# LIC_rack_BB-01.net
KiCad netlist of a schematic drawn in EAGLE
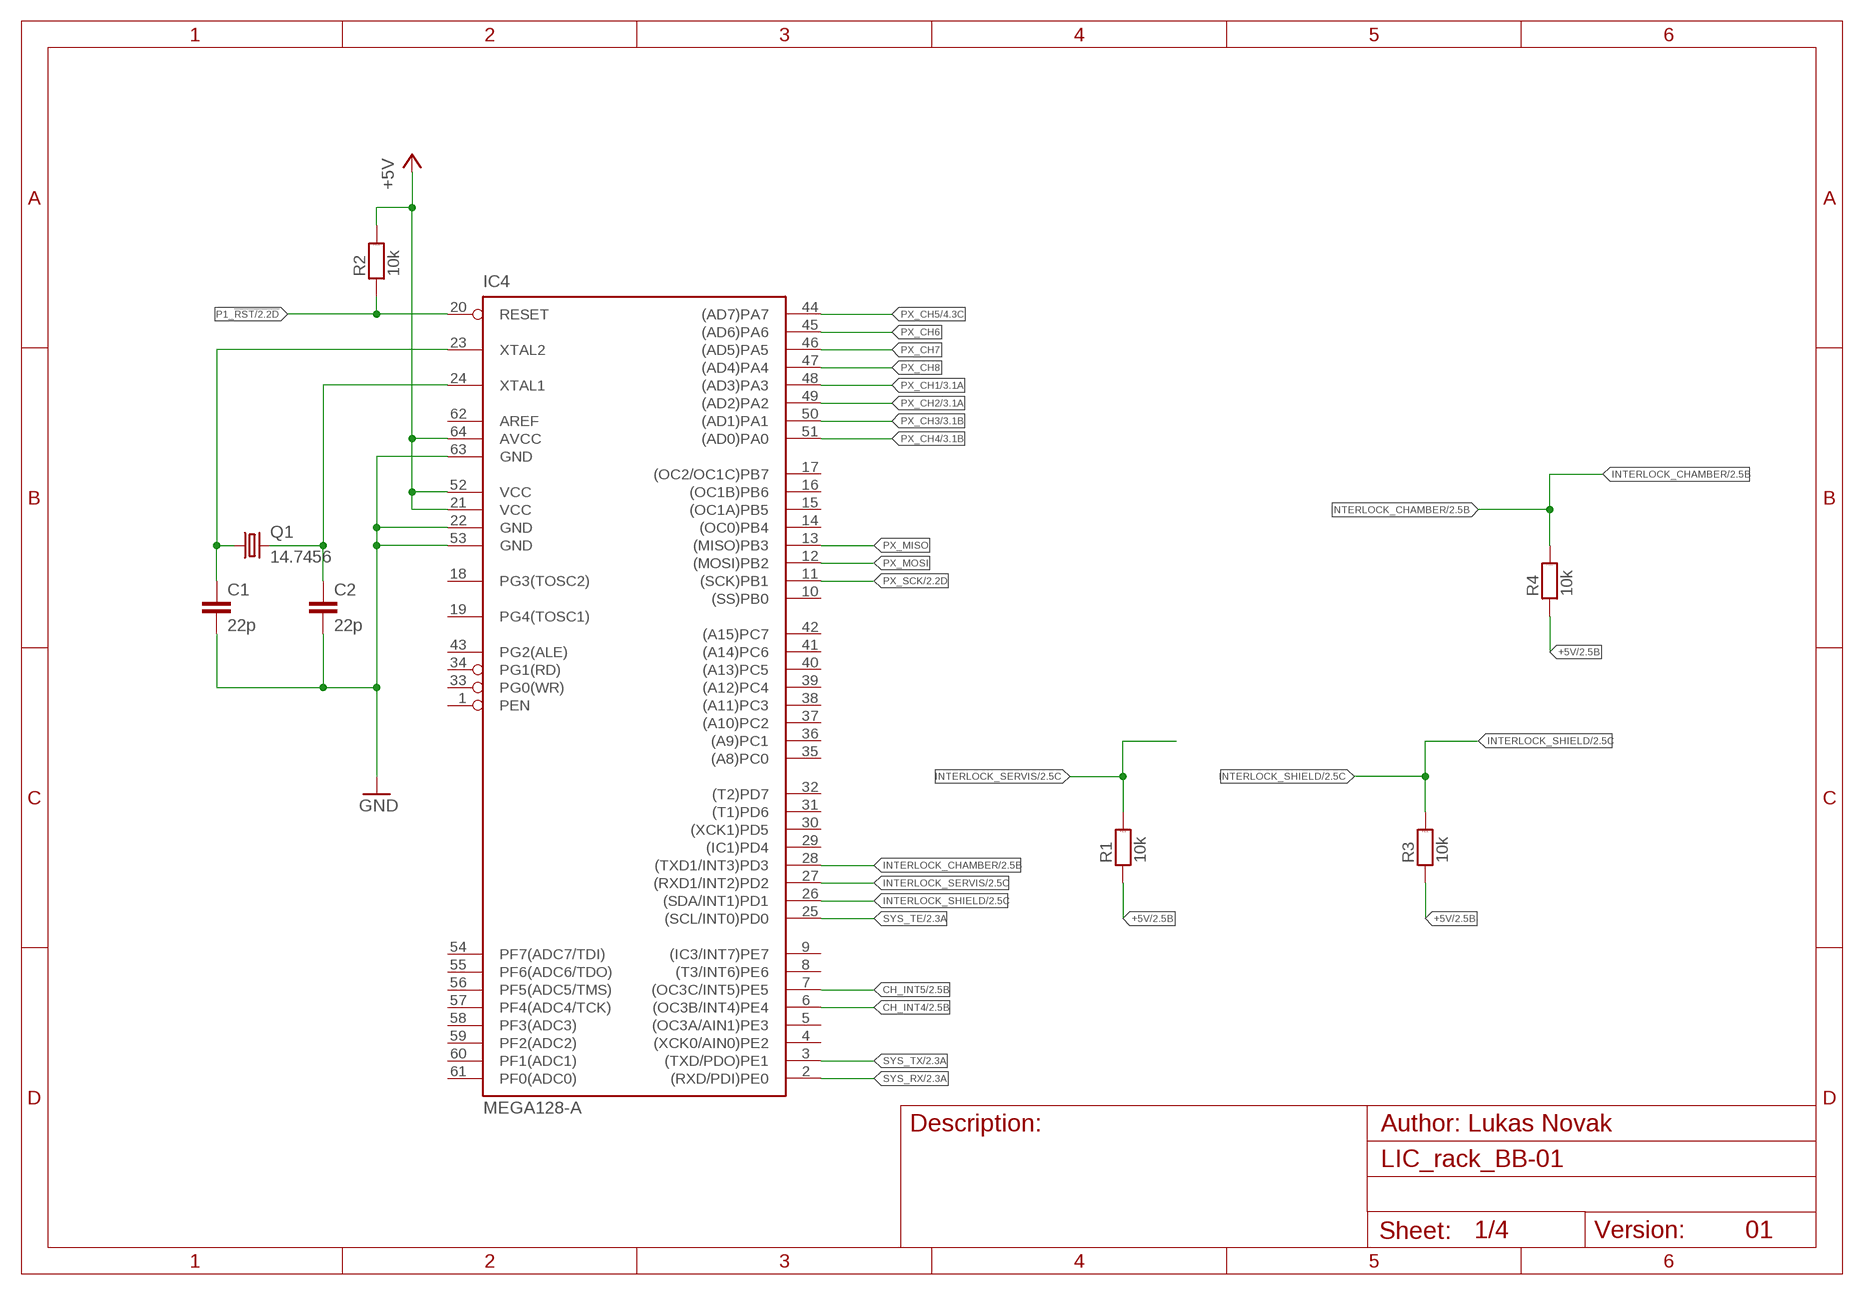
[diagram p0: schematic, sheet 1]
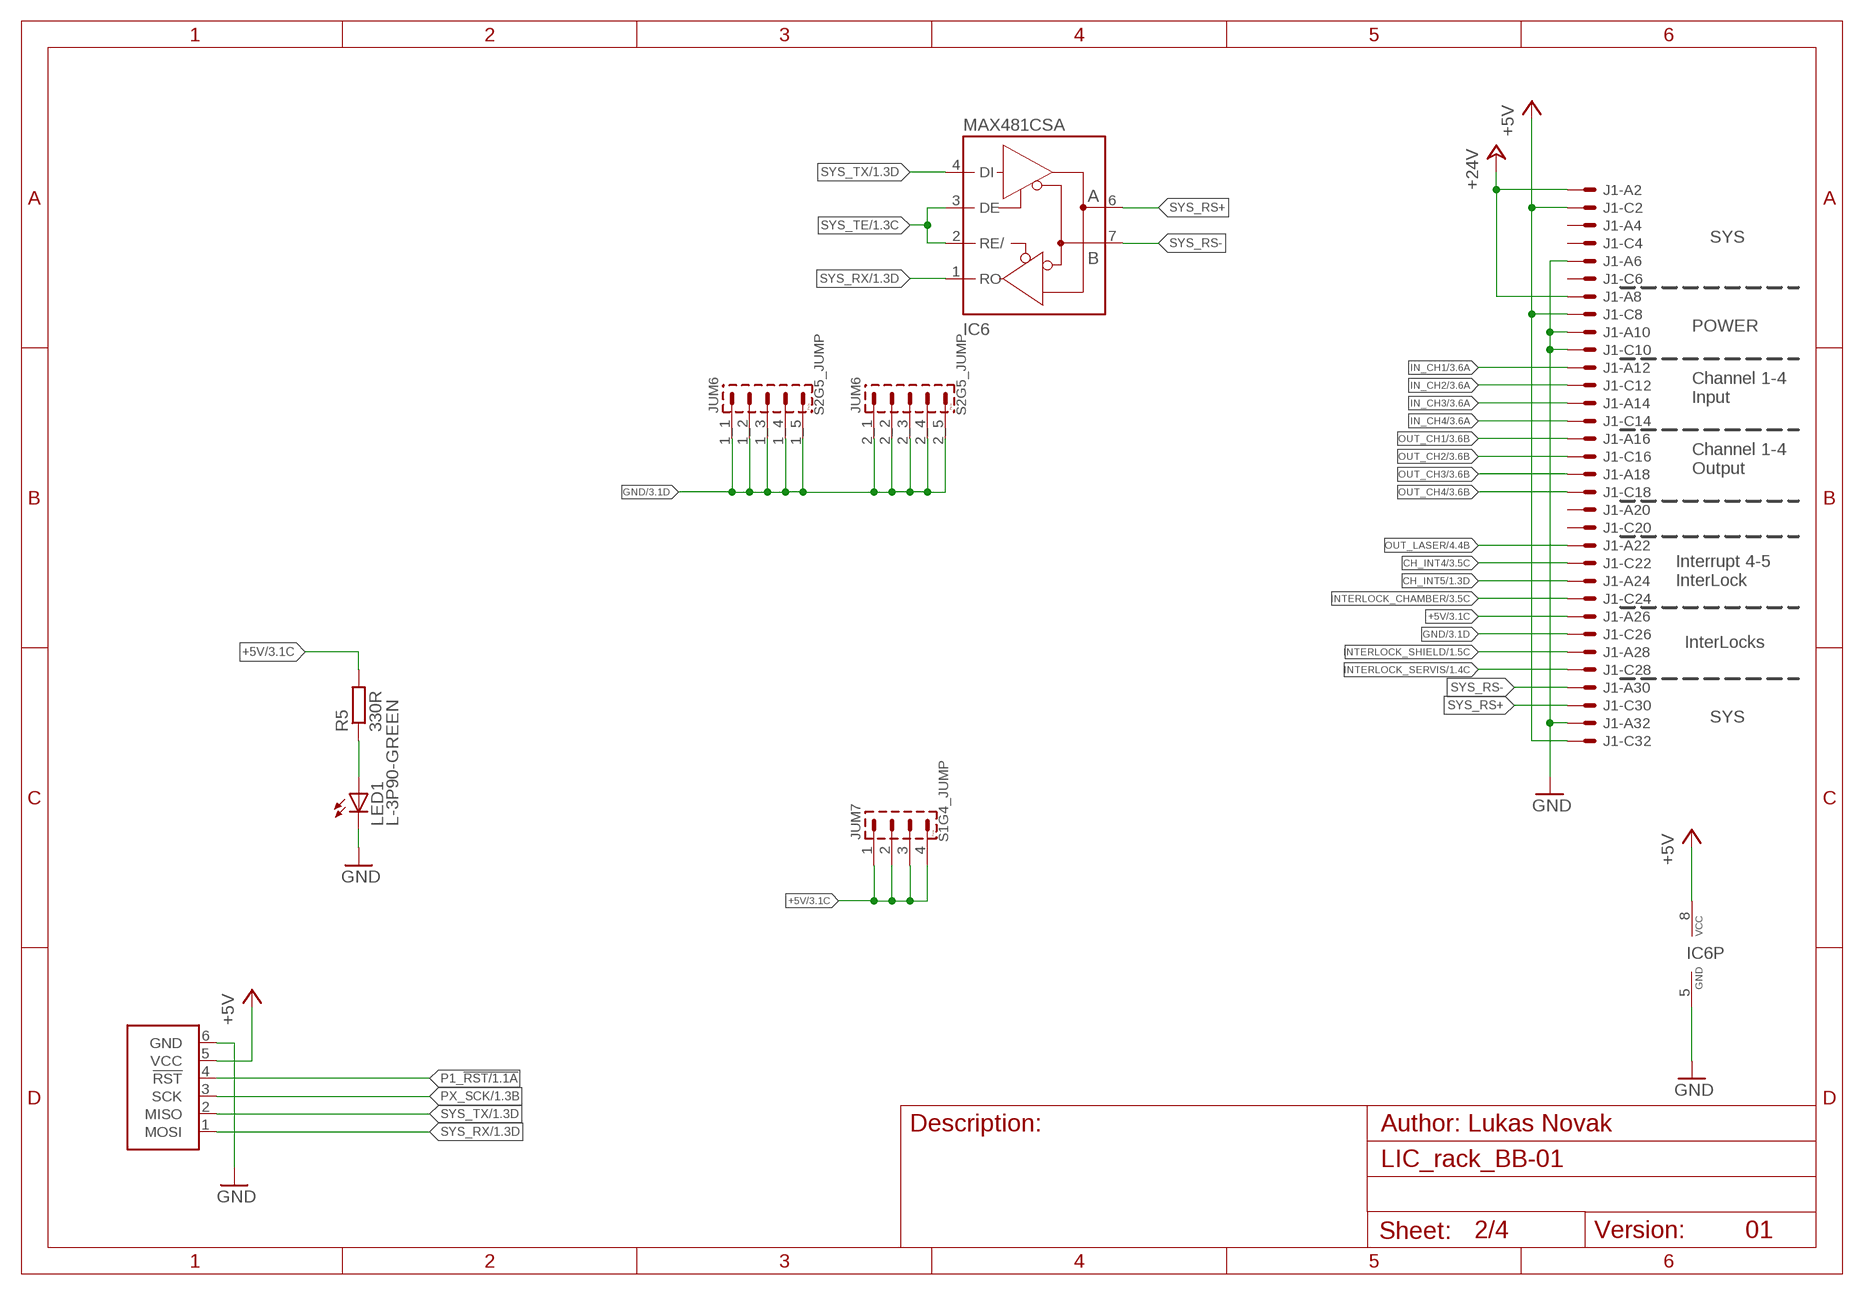
[diagram p1: schematic, sheet 2]
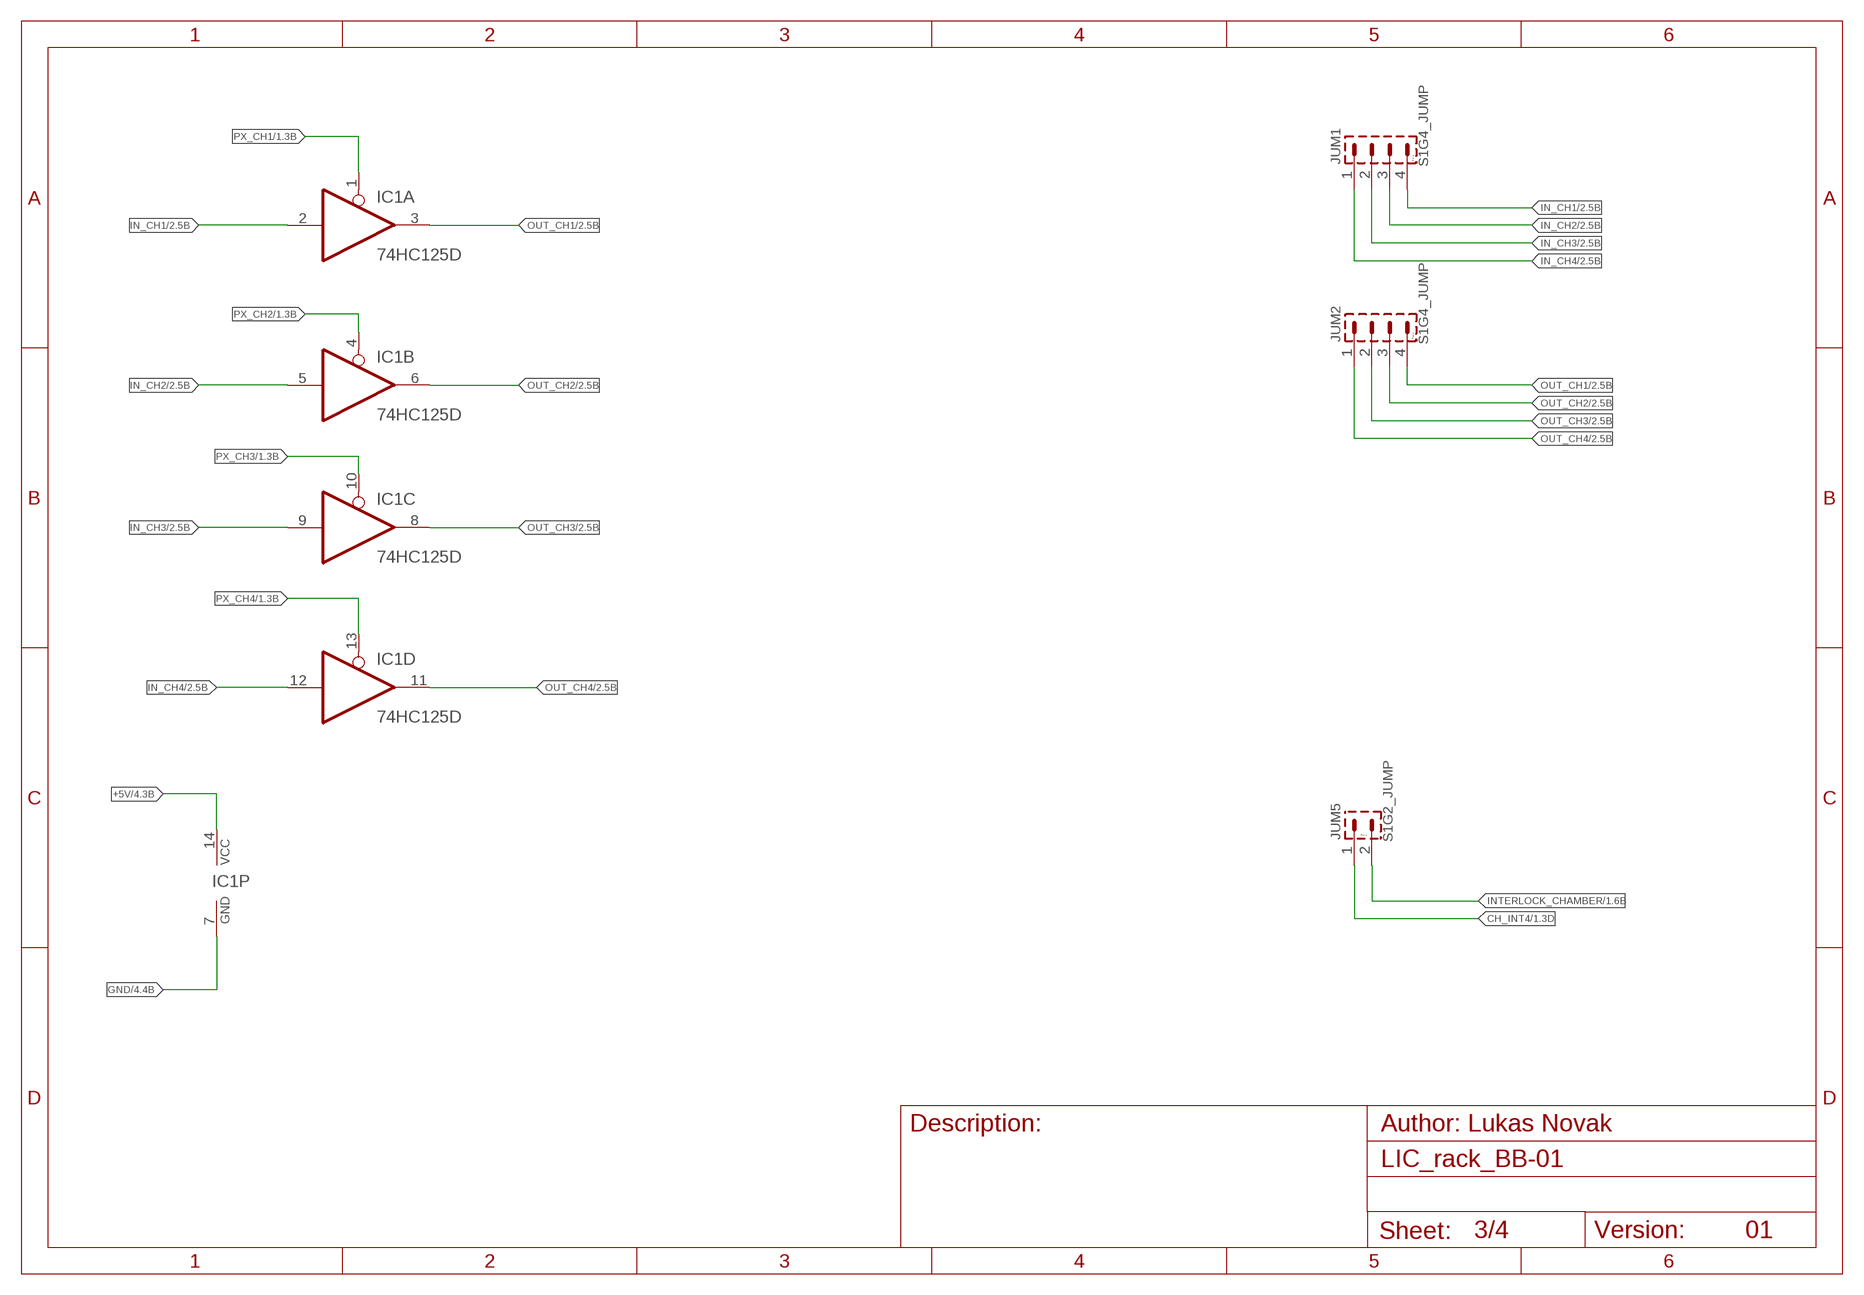
[diagram p2: schematic, sheet 3]
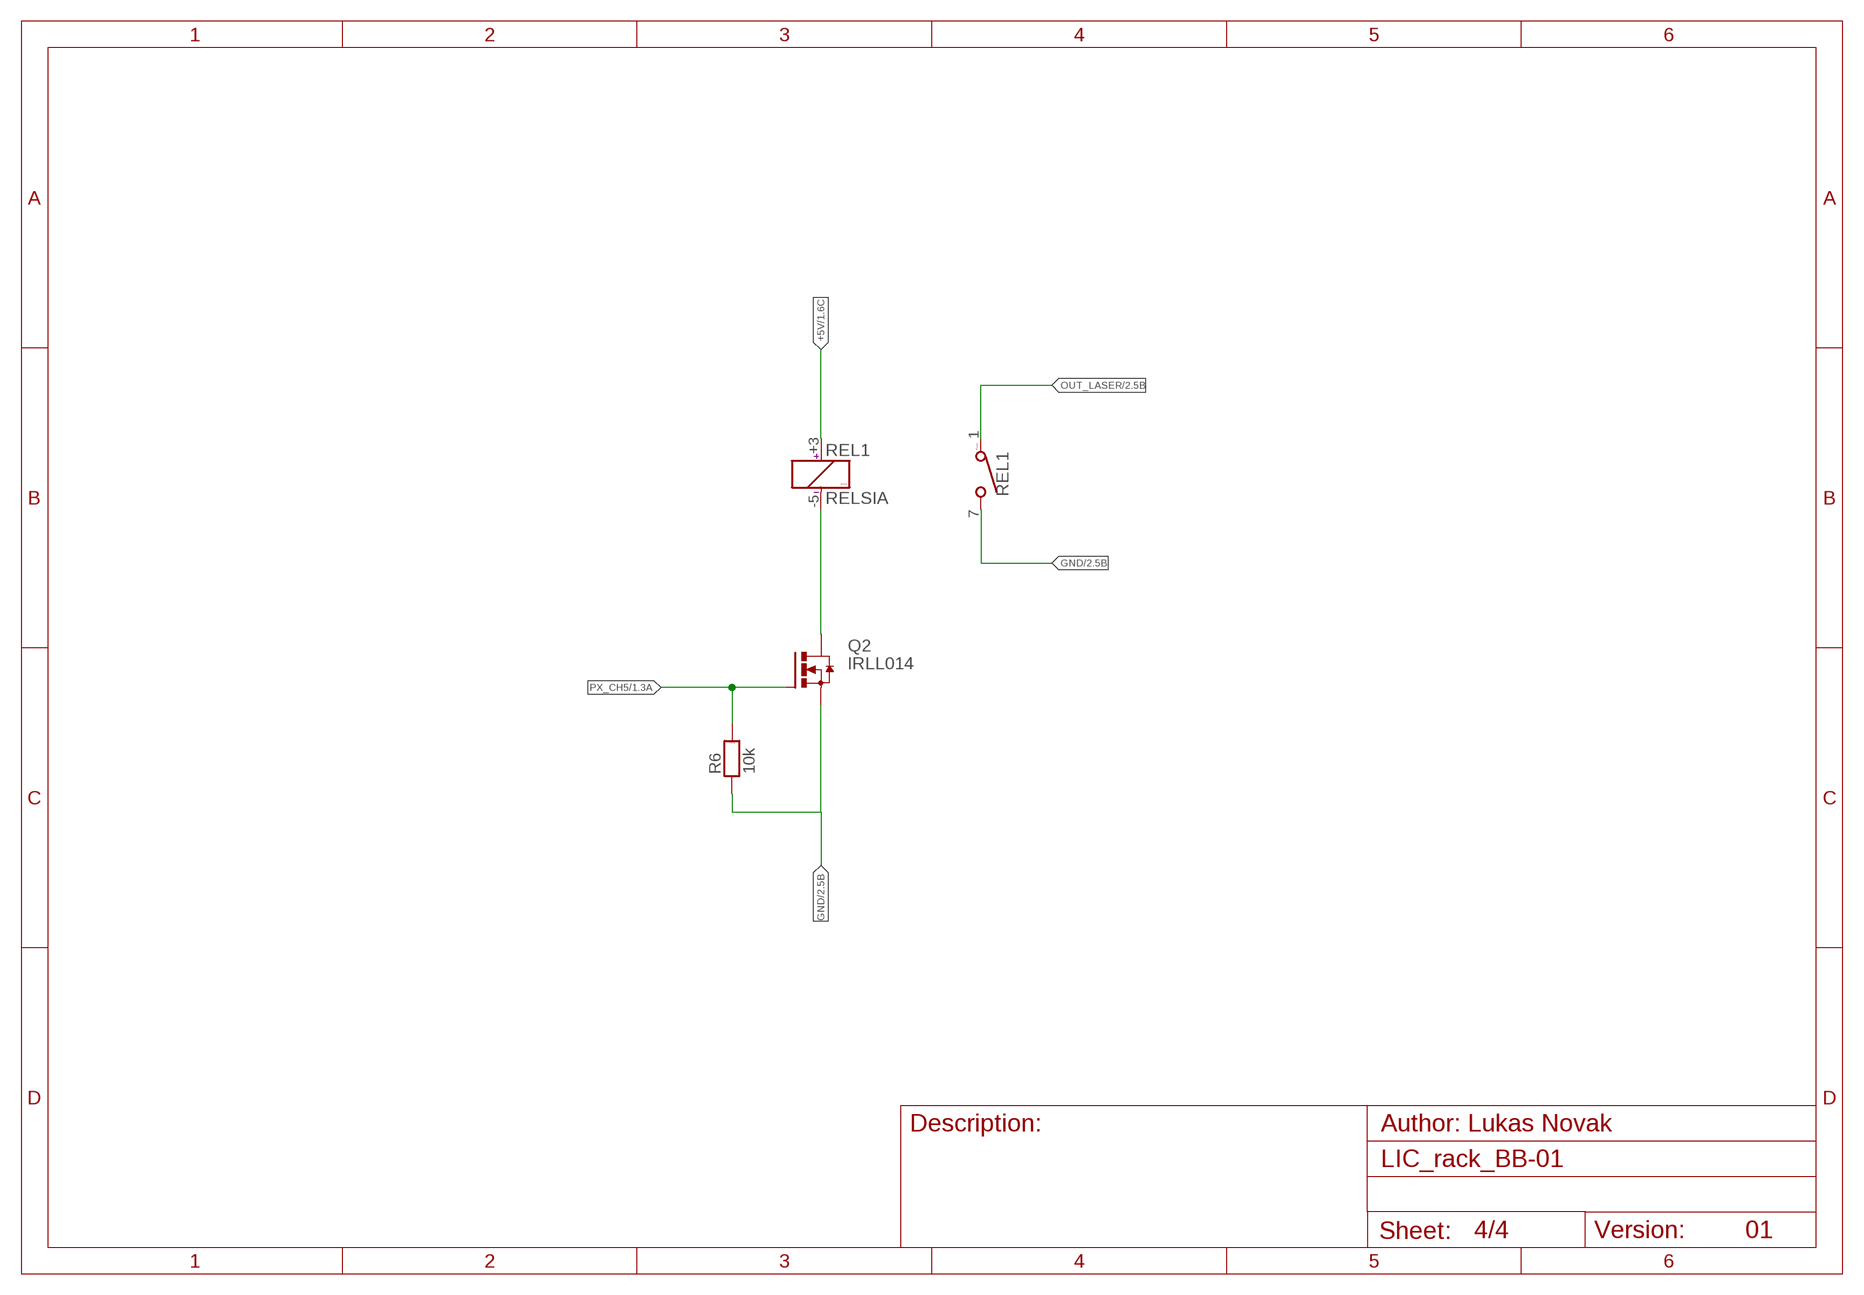
[diagram p3: schematic, sheet 4]

(export (version "E")
  (design (tool "Eeschema 10.0.6"))
  (components
    (comp (ref "Q2")
      (value "IRLL014")
      (footprint "eagle-import:SOT223")
      (libsource (lib "eagle-import") (part "N-HEXFET-2D_?-SOT232"))
    )
    (comp (ref "R6")
      (value "10k")
      (footprint "eagle-import:1206")
      (libsource (lib "eagle-import") (part "R_1206"))
    )
    (comp (ref "REL1")
      (value "RELSIA")
      (footprint "eagle-import:RELSIA")
      (libsource (lib "eagle-import") (part "RELSIA??"))
    )
    (comp (ref "C1")
      (value "22p")
      (footprint "eagle-import:C0805")
      (libsource (lib "eagle-import") (part "C-EUC0805"))
    )
    (comp (ref "C2")
      (value "22p")
      (footprint "eagle-import:C0805")
      (libsource (lib "eagle-import") (part "C-EUC0805"))
    )
    (comp (ref "IC4")
      (value "MEGA128-A")
      (footprint "eagle-import:TQFP64")
      (fields (field (name "MPN") "ATMEGA128-16AU"))
      (libsource (lib "eagle-import") (part "MEGA128-A"))
    )
    (comp (ref "Q1")
      (value "14.7456")
      (footprint "eagle-import:HC49U70")
      (libsource (lib "eagle-import") (part "XTAL"))
    )
    (comp (ref "R1")
      (value "10k")
      (footprint "eagle-import:1206")
      (libsource (lib "eagle-import") (part "R_1206"))
    )
    (comp (ref "R2")
      (value "10k")
      (footprint "eagle-import:1206")
      (libsource (lib "eagle-import") (part "R_1206"))
    )
    (comp (ref "R3")
      (value "10k")
      (footprint "eagle-import:1206")
      (libsource (lib "eagle-import") (part "R_1206"))
    )
    (comp (ref "R4")
      (value "10k")
      (footprint "eagle-import:1206")
      (libsource (lib "eagle-import") (part "R_1206"))
    )
    (comp (ref "IC6")
      (value "MAX481CSA")
      (footprint "eagle-import:SO08")
      (libsource (lib "eagle-import") (part "MAX481CSA"))
    )
    (comp (ref "J1")
      (value "VG32SP")
      (footprint "eagle-import:VG32P")
      (libsource (lib "eagle-import") (part "VG32SP"))
    )
    (comp (ref "JUM6")
      (value "S2G5_JUMP")
      (footprint "eagle-import:S2G5_JUM")
      (libsource (lib "eagle-import") (part "S2G5_JUMP"))
    )
    (comp (ref "JUM7")
      (value "S1G4_JUMP")
      (footprint "eagle-import:S1G4_JUM")
      (libsource (lib "eagle-import") (part "S1G4_JUMP"))
    )
    (comp (ref "LED1")
      (value "L-3P90-GREEN")
      (footprint "eagle-import:L-3P90")
      (libsource (lib "eagle-import") (part "L-3P90-GREEN"))
    )
    (comp (ref "R5")
      (value "330R")
      (footprint "eagle-import:R1206")
      (libsource (lib "eagle-import") (part "R-EU_R1206"))
    )
    (comp (ref "U1")
      (value "ATPROG-V")
      (footprint "eagle-import:6410-06")
      (libsource (lib "eagle-import") (part "ATPROG-V"))
    )
    (comp (ref "IC1")
      (value "74HC125D")
      (footprint "eagle-import:SO14")
      (libsource (lib "eagle-import") (part "74125DHC"))
    )
    (comp (ref "JUM1")
      (value "S1G4_JUMP")
      (footprint "eagle-import:S1G4_JUM")
      (libsource (lib "eagle-import") (part "S1G4_JUMP"))
    )
    (comp (ref "JUM2")
      (value "S1G4_JUMP")
      (footprint "eagle-import:S1G4_JUM")
      (libsource (lib "eagle-import") (part "S1G4_JUMP"))
    )
    (comp (ref "JUM5")
      (value "S1G2_JUMP")
      (footprint "eagle-import:S1G2_JUM")
      (libsource (lib "eagle-import") (part "S1G2_JUMP"))
    )
  )
  (nets
    (net (code "1") (name "+5V") (class "Default")
      (node (ref "IC1") (pin "14") (pinfunction "VCC_14") (pintype "power_in"))
      (node (ref "IC4") (pin "21") (pinfunction "VCC_21") (pintype "power_in"))
      (node (ref "IC4") (pin "52") (pinfunction "VCC_52") (pintype "power_in"))
      (node (ref "IC4") (pin "64") (pinfunction "AVCC_64") (pintype "power_in"))
      (node (ref "IC6") (pin "8") (pinfunction "VCC_8") (pintype "power_in"))
      (node (ref "J1") (pin "A26") (pinfunction "MS_A26") (pintype "passive"))
      (node (ref "J1") (pin "C2") (pinfunction "MS_C2") (pintype "passive"))
      (node (ref "J1") (pin "C32") (pinfunction "MSV_C32") (pintype "passive"))
      (node (ref "J1") (pin "C8") (pinfunction "MS_C8") (pintype "passive"))
      (node (ref "JUM7") (pin "1") (pinfunction "1_1") (pintype "passive"))
      (node (ref "JUM7") (pin "2") (pinfunction "2_2") (pintype "passive"))
      (node (ref "JUM7") (pin "3") (pinfunction "3_3") (pintype "passive"))
      (node (ref "JUM7") (pin "4") (pinfunction "4_4") (pintype "passive"))
      (node (ref "R1") (pin "1") (pinfunction "1_1") (pintype "passive"))
      (node (ref "R2") (pin "2") (pinfunction "2_2") (pintype "passive"))
      (node (ref "R3") (pin "1") (pinfunction "1_1") (pintype "passive"))
      (node (ref "R4") (pin "1") (pinfunction "1_1") (pintype "passive"))
      (node (ref "R5") (pin "2") (pinfunction "2_2") (pintype "passive"))
      (node (ref "REL1") (pin "+3") (pinfunction "C+_+3") (pintype "passive"))
      (node (ref "U1") (pin "5") (pinfunction "VCC_5") (pintype "power_in"))
    )
    (net (code "2") (name "+24V") (class "Default")
      (node (ref "J1") (pin "A2") (pinfunction "MS_A2") (pintype "passive"))
      (node (ref "J1") (pin "A8") (pinfunction "MS_A8") (pintype "passive"))
    )
    (net (code "3") (name "CH_INT4") (class "Default")
      (node (ref "IC4") (pin "6") (pinfunction "(OC3B/INT4)PE4_6") (pintype "bidirectional"))
      (node (ref "J1") (pin "C22") (pinfunction "MS_C22") (pintype "passive"))
      (node (ref "JUM5") (pin "1") (pinfunction "1_1") (pintype "passive"))
    )
    (net (code "4") (name "CH_INT5") (class "Default")
      (node (ref "IC4") (pin "7") (pinfunction "(OC3C/INT5)PE5_7") (pintype "bidirectional"))
      (node (ref "J1") (pin "A24") (pinfunction "MS_A24") (pintype "passive"))
    )
    (net (code "5") (name "GND") (class "Default")
      (node (ref "C1") (pin "2") (pinfunction "2_2") (pintype "passive"))
      (node (ref "C2") (pin "2") (pinfunction "2_2") (pintype "passive"))
      (node (ref "IC1") (pin "7") (pinfunction "GND_7") (pintype "power_in"))
      (node (ref "IC4") (pin "22") (pinfunction "GND_22") (pintype "power_in"))
      (node (ref "IC4") (pin "53") (pinfunction "GND_53") (pintype "power_in"))
      (node (ref "IC4") (pin "63") (pinfunction "GND_63") (pintype "power_in"))
      (node (ref "IC6") (pin "5") (pinfunction "GND_5") (pintype "power_in"))
      (node (ref "J1") (pin "A10") (pinfunction "MS_A10") (pintype "passive"))
      (node (ref "J1") (pin "A32") (pinfunction "MS_A32") (pintype "passive"))
      (node (ref "J1") (pin "A6") (pinfunction "MS_A6") (pintype "passive"))
      (node (ref "J1") (pin "C10") (pinfunction "MS_C10") (pintype "passive"))
      (node (ref "J1") (pin "C26") (pinfunction "MS_C26") (pintype "passive"))
      (node (ref "JUM6") (pin "1_1") (pinfunction "1_1_1") (pintype "passive"))
      (node (ref "JUM6") (pin "1_2") (pinfunction "2_1_2") (pintype "passive"))
      (node (ref "JUM6") (pin "1_3") (pinfunction "3_1_3") (pintype "passive"))
      (node (ref "JUM6") (pin "1_4") (pinfunction "4_1_4") (pintype "passive"))
      (node (ref "JUM6") (pin "1_5") (pinfunction "5_1_5") (pintype "passive"))
      (node (ref "JUM6") (pin "2_1") (pinfunction "1_2_1") (pintype "passive"))
      (node (ref "JUM6") (pin "2_2") (pinfunction "2_2_2") (pintype "passive"))
      (node (ref "JUM6") (pin "2_3") (pinfunction "3_2_3") (pintype "passive"))
      (node (ref "JUM6") (pin "2_4") (pinfunction "4_2_4") (pintype "passive"))
      (node (ref "JUM6") (pin "2_5") (pinfunction "5_2_5") (pintype "passive"))
      (node (ref "LED1") (pin "K") (pinfunction "C_K") (pintype "passive"))
      (node (ref "Q2") (pin "3") (pinfunction "S_3") (pintype "passive"))
      (node (ref "R6") (pin "1") (pinfunction "1_1") (pintype "passive"))
      (node (ref "REL1") (pin "7") (pinfunction "2_7") (pintype "passive"))
      (node (ref "U1") (pin "6") (pinfunction "GND_6") (pintype "power_in"))
    )
    (net (code "6") (name "INTERLOCK_CHAMBER") (class "Default")
      (node (ref "IC4") (pin "28") (pinfunction "(TXD1/INT3)PD3_28") (pintype "bidirectional"))
      (node (ref "J1") (pin "C24") (pinfunction "MS_C24") (pintype "passive"))
      (node (ref "JUM5") (pin "2") (pinfunction "2_2") (pintype "passive"))
      (node (ref "R4") (pin "2") (pinfunction "2_2") (pintype "passive"))
    )
    (net (code "7") (name "INTERLOCK_SERVIS") (class "Default")
      (node (ref "IC4") (pin "27") (pinfunction "(RXD1/INT2)PD2_27") (pintype "bidirectional"))
      (node (ref "J1") (pin "C28") (pinfunction "MS_C28") (pintype "passive"))
      (node (ref "R1") (pin "2") (pinfunction "2_2") (pintype "passive"))
    )
    (net (code "8") (name "INTERLOCK_SHIELD") (class "Default")
      (node (ref "IC4") (pin "26") (pinfunction "(SDA/INT1)PD1_26") (pintype "bidirectional"))
      (node (ref "J1") (pin "A28") (pinfunction "MS_A28") (pintype "passive"))
      (node (ref "R3") (pin "2") (pinfunction "2_2") (pintype "passive"))
    )
    (net (code "9") (name "IN_CH1") (class "Default")
      (node (ref "IC1") (pin "2") (pinfunction "I_2") (pintype "input"))
      (node (ref "J1") (pin "A12") (pinfunction "MS_A12") (pintype "passive"))
      (node (ref "JUM1") (pin "4") (pinfunction "4_4") (pintype "passive"))
    )
    (net (code "10") (name "IN_CH2") (class "Default")
      (node (ref "IC1") (pin "5") (pinfunction "I_5") (pintype "input"))
      (node (ref "J1") (pin "C12") (pinfunction "MS_C12") (pintype "passive"))
      (node (ref "JUM1") (pin "3") (pinfunction "3_3") (pintype "passive"))
    )
    (net (code "11") (name "IN_CH3") (class "Default")
      (node (ref "IC1") (pin "9") (pinfunction "I_9") (pintype "input"))
      (node (ref "J1") (pin "A14") (pinfunction "MS_A14") (pintype "passive"))
      (node (ref "JUM1") (pin "2") (pinfunction "2_2") (pintype "passive"))
    )
    (net (code "12") (name "IN_CH4") (class "Default")
      (node (ref "IC1") (pin "12") (pinfunction "I_12") (pintype "input"))
      (node (ref "J1") (pin "C14") (pinfunction "MS_C14") (pintype "passive"))
      (node (ref "JUM1") (pin "1") (pinfunction "1_1") (pintype "passive"))
    )
    (net (code "13") (name "Net-(IC4-XTAL1)") (class "Default")
      (node (ref "C2") (pin "1") (pinfunction "1_1") (pintype "passive"))
      (node (ref "IC4") (pin "24") (pinfunction "XTAL1_24") (pintype "bidirectional"))
      (node (ref "Q1") (pin "2") (pinfunction "2_2") (pintype "passive"))
    )
    (net (code "14") (name "Net-(IC4-XTAL2)") (class "Default")
      (node (ref "C1") (pin "1") (pinfunction "1_1") (pintype "passive"))
      (node (ref "IC4") (pin "23") (pinfunction "XTAL2_23") (pintype "bidirectional"))
      (node (ref "Q1") (pin "1") (pinfunction "1_1") (pintype "passive"))
    )
    (net (code "15") (name "Net-(LED1-PadA)") (class "Default")
      (node (ref "LED1") (pin "A") (pinfunction "A_A") (pintype "passive"))
      (node (ref "R5") (pin "1") (pinfunction "1_1") (pintype "passive"))
    )
    (net (code "16") (name "Net-(REL1A-C-)") (class "Default")
      (node (ref "Q2") (pin "2") (pinfunction "D_2") (pintype "passive"))
      (node (ref "Q2") (pin "4") (pinfunction "D_4") (pintype "passive"))
      (node (ref "REL1") (pin "-5") (pinfunction "C-_-5") (pintype "passive"))
    )
    (net (code "17") (name "OUT_CH1") (class "Default")
      (node (ref "IC1") (pin "3") (pinfunction "O_3") (pintype "tri_state"))
      (node (ref "J1") (pin "A16") (pinfunction "MS_A16") (pintype "passive"))
      (node (ref "JUM2") (pin "4") (pinfunction "4_4") (pintype "passive"))
    )
    (net (code "18") (name "OUT_CH2") (class "Default")
      (node (ref "IC1") (pin "6") (pinfunction "O_6") (pintype "tri_state"))
      (node (ref "J1") (pin "C16") (pinfunction "MS_C16") (pintype "passive"))
      (node (ref "JUM2") (pin "3") (pinfunction "3_3") (pintype "passive"))
    )
    (net (code "19") (name "OUT_CH3") (class "Default")
      (node (ref "IC1") (pin "8") (pinfunction "O_8") (pintype "tri_state"))
      (node (ref "J1") (pin "A18") (pinfunction "MS_A18") (pintype "passive"))
      (node (ref "JUM2") (pin "2") (pinfunction "2_2") (pintype "passive"))
    )
    (net (code "20") (name "OUT_CH4") (class "Default")
      (node (ref "IC1") (pin "11") (pinfunction "O_11") (pintype "tri_state"))
      (node (ref "J1") (pin "C18") (pinfunction "MS_C18") (pintype "passive"))
      (node (ref "JUM2") (pin "1") (pinfunction "1_1") (pintype "passive"))
    )
    (net (code "21") (name "OUT_LASER") (class "Default")
      (node (ref "J1") (pin "A22") (pinfunction "MS_A22") (pintype "passive"))
      (node (ref "REL1") (pin "1") (pinfunction "1_1") (pintype "passive"))
    )
    (net (code "22") (name "P1_~{RST}") (class "Default")
      (node (ref "IC4") (pin "20") (pinfunction "RESET_20") (pintype "input"))
      (node (ref "R2") (pin "1") (pinfunction "1_1") (pintype "passive"))
      (node (ref "U1") (pin "4") (pinfunction "~{RST}_4") (pintype "input"))
    )
    (net (code "23") (name "PX_CH1") (class "Default")
      (node (ref "IC1") (pin "1") (pinfunction "OE_1") (pintype "input"))
      (node (ref "IC4") (pin "48") (pinfunction "(AD3)PA3_48") (pintype "bidirectional"))
    )
    (net (code "24") (name "PX_CH2") (class "Default")
      (node (ref "IC1") (pin "4") (pinfunction "OE_4") (pintype "input"))
      (node (ref "IC4") (pin "49") (pinfunction "(AD2)PA2_49") (pintype "bidirectional"))
    )
    (net (code "25") (name "PX_CH3") (class "Default")
      (node (ref "IC1") (pin "10") (pinfunction "OE_10") (pintype "input"))
      (node (ref "IC4") (pin "50") (pinfunction "(AD1)PA1_50") (pintype "bidirectional"))
    )
    (net (code "26") (name "PX_CH4") (class "Default")
      (node (ref "IC1") (pin "13") (pinfunction "OE_13") (pintype "input"))
      (node (ref "IC4") (pin "51") (pinfunction "(AD0)PA0_51") (pintype "bidirectional"))
    )
    (net (code "27") (name "PX_CH5") (class "Default")
      (node (ref "IC4") (pin "44") (pinfunction "(AD7)PA7_44") (pintype "bidirectional"))
      (node (ref "Q2") (pin "1") (pinfunction "G_1") (pintype "passive"))
      (node (ref "R6") (pin "2") (pinfunction "2_2") (pintype "passive"))
    )
    (net (code "28") (name "PX_CH6") (class "Default")
      (node (ref "IC4") (pin "45") (pinfunction "(AD6)PA6_45") (pintype "bidirectional"))
    )
    (net (code "29") (name "PX_CH7") (class "Default")
      (node (ref "IC4") (pin "46") (pinfunction "(AD5)PA5_46") (pintype "bidirectional"))
    )
    (net (code "30") (name "PX_CH8") (class "Default")
      (node (ref "IC4") (pin "47") (pinfunction "(AD4)PA4_47") (pintype "bidirectional"))
    )
    (net (code "31") (name "PX_MISO") (class "Default")
      (node (ref "IC4") (pin "13") (pinfunction "(MISO)PB3_13") (pintype "bidirectional"))
    )
    (net (code "32") (name "PX_MOSI") (class "Default")
      (node (ref "IC4") (pin "12") (pinfunction "(MOSI)PB2_12") (pintype "bidirectional"))
    )
    (net (code "33") (name "PX_SCK") (class "Default")
      (node (ref "IC4") (pin "11") (pinfunction "(SCK)PB1_11") (pintype "bidirectional"))
      (node (ref "U1") (pin "3") (pinfunction "SCK_3") (pintype "input"))
    )
    (net (code "34") (name "SYS_RS+") (class "Default")
      (node (ref "IC6") (pin "6") (pinfunction "A_6") (pintype "passive"))
      (node (ref "J1") (pin "C30") (pinfunction "MS_C30") (pintype "passive"))
    )
    (net (code "35") (name "SYS_RS-") (class "Default")
      (node (ref "IC6") (pin "7") (pinfunction "B_7") (pintype "passive"))
      (node (ref "J1") (pin "A30") (pinfunction "MS_A30") (pintype "passive"))
    )
    (net (code "36") (name "SYS_RX") (class "Default")
      (node (ref "IC4") (pin "2") (pinfunction "(RXD/PDI)PE0_2") (pintype "bidirectional"))
      (node (ref "IC6") (pin "1") (pinfunction "RO_1") (pintype "output"))
      (node (ref "U1") (pin "1") (pinfunction "MOSI_1") (pintype "output"))
    )
    (net (code "37") (name "SYS_TE") (class "Default")
      (node (ref "IC4") (pin "25") (pinfunction "(SCL/INT0)PD0_25") (pintype "bidirectional"))
      (node (ref "IC6") (pin "2") (pinfunction "RE/_2") (pintype "input"))
      (node (ref "IC6") (pin "3") (pinfunction "DE_3") (pintype "input"))
    )
    (net (code "38") (name "SYS_TX") (class "Default")
      (node (ref "IC4") (pin "3") (pinfunction "(TXD/PDO)PE1_3") (pintype "bidirectional"))
      (node (ref "IC6") (pin "4") (pinfunction "DI_4") (pintype "input"))
      (node (ref "U1") (pin "2") (pinfunction "MISO_2") (pintype "input"))
    )
    (net (code "39") (name "unconnected-(IC4-(A8)PC0-Pad35)") (class "Default")
      (node (ref "IC4") (pin "35") (pinfunction "(A8)PC0_35") (pintype "output"))
    )
    (net (code "40") (name "unconnected-(IC4-(A9)PC1-Pad36)") (class "Default")
      (node (ref "IC4") (pin "36") (pinfunction "(A9)PC1_36") (pintype "output"))
    )
    (net (code "41") (name "unconnected-(IC4-(A10)PC2-Pad37)") (class "Default")
      (node (ref "IC4") (pin "37") (pinfunction "(A10)PC2_37") (pintype "output"))
    )
    (net (code "42") (name "unconnected-(IC4-(A11)PC3-Pad38)") (class "Default")
      (node (ref "IC4") (pin "38") (pinfunction "(A11)PC3_38") (pintype "output"))
    )
    (net (code "43") (name "unconnected-(IC4-(A12)PC4-Pad39)") (class "Default")
      (node (ref "IC4") (pin "39") (pinfunction "(A12)PC4_39") (pintype "output"))
    )
    (net (code "44") (name "unconnected-(IC4-(A13)PC5-Pad40)") (class "Default")
      (node (ref "IC4") (pin "40") (pinfunction "(A13)PC5_40") (pintype "output"))
    )
    (net (code "45") (name "unconnected-(IC4-(A14)PC6-Pad41)") (class "Default")
      (node (ref "IC4") (pin "41") (pinfunction "(A14)PC6_41") (pintype "output"))
    )
    (net (code "46") (name "unconnected-(IC4-(A15)PC7-Pad42)") (class "Default")
      (node (ref "IC4") (pin "42") (pinfunction "(A15)PC7_42") (pintype "output"))
    )
    (net (code "47") (name "unconnected-(IC4-(IC1)PD4-Pad29)") (class "Default")
      (node (ref "IC4") (pin "29") (pinfunction "(IC1)PD4_29") (pintype "bidirectional"))
    )
    (net (code "48") (name "unconnected-(IC4-(IC3{slash}INT7)PE7-Pad9)") (class "Default")
      (node (ref "IC4") (pin "9") (pinfunction "(IC3/INT7)PE7_9") (pintype "bidirectional"))
    )
    (net (code "49") (name "unconnected-(IC4-(OC0)PB4-Pad14)") (class "Default")
      (node (ref "IC4") (pin "14") (pinfunction "(OC0)PB4_14") (pintype "bidirectional"))
    )
    (net (code "50") (name "unconnected-(IC4-(OC1A)PB5-Pad15)") (class "Default")
      (node (ref "IC4") (pin "15") (pinfunction "(OC1A)PB5_15") (pintype "bidirectional"))
    )
    (net (code "51") (name "unconnected-(IC4-(OC1B)PB6-Pad16)") (class "Default")
      (node (ref "IC4") (pin "16") (pinfunction "(OC1B)PB6_16") (pintype "bidirectional"))
    )
    (net (code "52") (name "unconnected-(IC4-(OC2{slash}OC1C)PB7-Pad17)") (class "Default")
      (node (ref "IC4") (pin "17") (pinfunction "(OC2/OC1C)PB7_17") (pintype "bidirectional"))
    )
    (net (code "53") (name "unconnected-(IC4-(OC3A{slash}AIN1)PE3-Pad5)") (class "Default")
      (node (ref "IC4") (pin "5") (pinfunction "(OC3A/AIN1)PE3_5") (pintype "bidirectional"))
    )
    (net (code "54") (name "unconnected-(IC4-(SS)PB0-Pad10)") (class "Default")
      (node (ref "IC4") (pin "10") (pinfunction "(SS)PB0_10") (pintype "bidirectional"))
    )
    (net (code "55") (name "unconnected-(IC4-(T1)PD6-Pad31)") (class "Default")
      (node (ref "IC4") (pin "31") (pinfunction "(T1)PD6_31") (pintype "bidirectional"))
    )
    (net (code "56") (name "unconnected-(IC4-(T2)PD7-Pad32)") (class "Default")
      (node (ref "IC4") (pin "32") (pinfunction "(T2)PD7_32") (pintype "bidirectional"))
    )
    (net (code "57") (name "unconnected-(IC4-(T3{slash}INT6)PE6-Pad8)") (class "Default")
      (node (ref "IC4") (pin "8") (pinfunction "(T3/INT6)PE6_8") (pintype "bidirectional"))
    )
    (net (code "58") (name "unconnected-(IC4-(XCK0{slash}AIN0)PE2-Pad4)") (class "Default")
      (node (ref "IC4") (pin "4") (pinfunction "(XCK0/AIN0)PE2_4") (pintype "bidirectional"))
    )
    (net (code "59") (name "unconnected-(IC4-(XCK1)PD5-Pad30)") (class "Default")
      (node (ref "IC4") (pin "30") (pinfunction "(XCK1)PD5_30") (pintype "bidirectional"))
    )
    (net (code "60") (name "unconnected-(IC4-AREF-Pad62)") (class "Default")
      (node (ref "IC4") (pin "62") (pinfunction "AREF_62") (pintype "passive"))
    )
    (net (code "61") (name "unconnected-(IC4-PEN-Pad1)") (class "Default")
      (node (ref "IC4") (pin "1") (pinfunction "PEN_1") (pintype "input"))
    )
    (net (code "62") (name "unconnected-(IC4-PF0(ADC0)-Pad61)") (class "Default")
      (node (ref "IC4") (pin "61") (pinfunction "PF0(ADC0)_61") (pintype "input"))
    )
    (net (code "63") (name "unconnected-(IC4-PF1(ADC1)-Pad60)") (class "Default")
      (node (ref "IC4") (pin "60") (pinfunction "PF1(ADC1)_60") (pintype "input"))
    )
    (net (code "64") (name "unconnected-(IC4-PF2(ADC2)-Pad59)") (class "Default")
      (node (ref "IC4") (pin "59") (pinfunction "PF2(ADC2)_59") (pintype "input"))
    )
    (net (code "65") (name "unconnected-(IC4-PF3(ADC3)-Pad58)") (class "Default")
      (node (ref "IC4") (pin "58") (pinfunction "PF3(ADC3)_58") (pintype "input"))
    )
    (net (code "66") (name "unconnected-(IC4-PF4(ADC4{slash}TCK)-Pad57)") (class "Default")
      (node (ref "IC4") (pin "57") (pinfunction "PF4(ADC4/TCK)_57") (pintype "input"))
    )
    (net (code "67") (name "unconnected-(IC4-PF5(ADC5{slash}TMS)-Pad56)") (class "Default")
      (node (ref "IC4") (pin "56") (pinfunction "PF5(ADC5/TMS)_56") (pintype "input"))
    )
    (net (code "68") (name "unconnected-(IC4-PF6(ADC6{slash}TDO)-Pad55)") (class "Default")
      (node (ref "IC4") (pin "55") (pinfunction "PF6(ADC6/TDO)_55") (pintype "input"))
    )
    (net (code "69") (name "unconnected-(IC4-PF7(ADC7{slash}TDI)-Pad54)") (class "Default")
      (node (ref "IC4") (pin "54") (pinfunction "PF7(ADC7/TDI)_54") (pintype "input"))
    )
    (net (code "70") (name "unconnected-(IC4-PG0(WR)-Pad33)") (class "Default")
      (node (ref "IC4") (pin "33") (pinfunction "PG0(WR)_33") (pintype "bidirectional"))
    )
    (net (code "71") (name "unconnected-(IC4-PG1(RD)-Pad34)") (class "Default")
      (node (ref "IC4") (pin "34") (pinfunction "PG1(RD)_34") (pintype "bidirectional"))
    )
    (net (code "72") (name "unconnected-(IC4-PG2(ALE)-Pad43)") (class "Default")
      (node (ref "IC4") (pin "43") (pinfunction "PG2(ALE)_43") (pintype "bidirectional"))
    )
    (net (code "73") (name "unconnected-(IC4-PG3(TOSC2)-Pad18)") (class "Default")
      (node (ref "IC4") (pin "18") (pinfunction "PG3(TOSC2)_18") (pintype "bidirectional"))
    )
    (net (code "74") (name "unconnected-(IC4-PG4(TOSC1)-Pad19)") (class "Default")
      (node (ref "IC4") (pin "19") (pinfunction "PG4(TOSC1)_19") (pintype "bidirectional"))
    )
    (net (code "75") (name "unconnected-(J1AD-MS-PadC4)") (class "Default")
      (node (ref "J1") (pin "C4") (pinfunction "MS_C4") (pintype "passive"))
    )
    (net (code "76") (name "unconnected-(J1AE-MS-PadC6)") (class "Default")
      (node (ref "J1") (pin "C6") (pinfunction "MS_C6") (pintype "passive"))
    )
    (net (code "77") (name "unconnected-(J1G-MS-PadA20)") (class "Default")
      (node (ref "J1") (pin "A20") (pinfunction "MS_A20") (pintype "passive"))
    )
    (net (code "78") (name "unconnected-(J1N-MS-PadA4)") (class "Default")
      (node (ref "J1") (pin "A4") (pinfunction "MS_A4") (pintype "passive"))
    )
    (net (code "79") (name "unconnected-(J1W-MS-PadC20)") (class "Default")
      (node (ref "J1") (pin "C20") (pinfunction "MS_C20") (pintype "passive"))
    )
  )
)
